# ElectronicATU.net
KiCad netlist of a schematic drawn in EAGLE
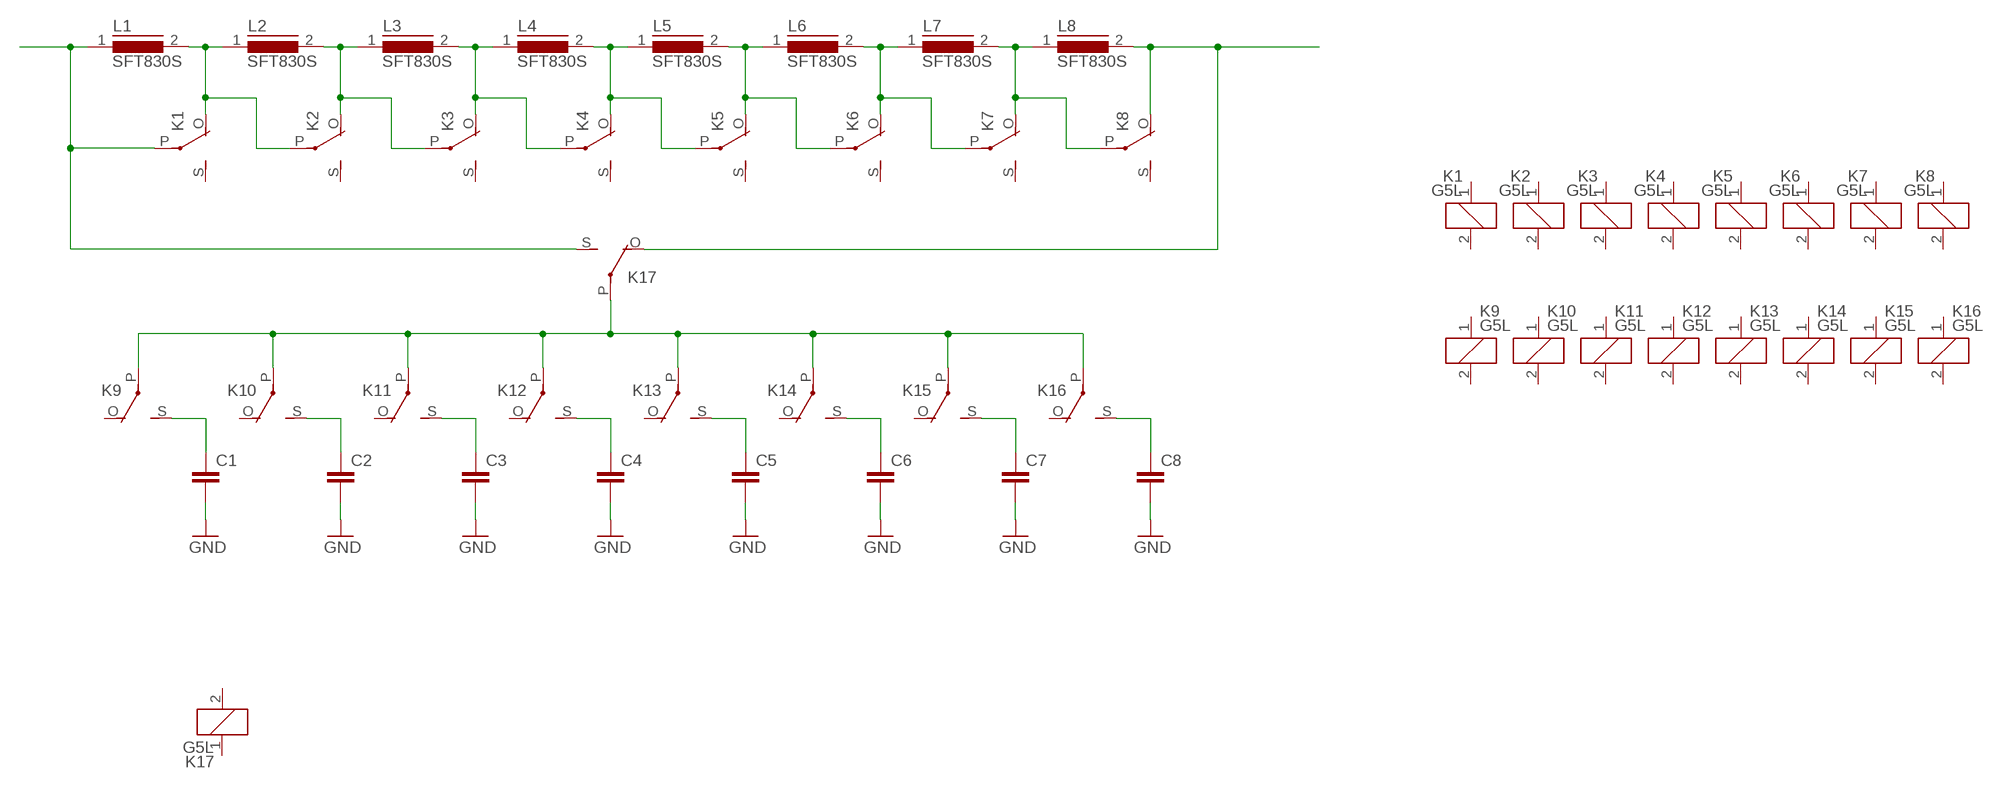
[diagram p0: schematic, sheet 1]

(export (version "E")
  (design (tool "Eeschema 10.0.6"))
  (components
    (comp (ref "C1")
      (value "C-EU075-042X103")
      (footprint "eagle-import:C075-042X103")
      (libsource (lib "eagle-import") (part "C-EU075-042X103"))
    )
    (comp (ref "C2")
      (value "C-EU075-042X103")
      (footprint "eagle-import:C075-042X103")
      (libsource (lib "eagle-import") (part "C-EU075-042X103"))
    )
    (comp (ref "C3")
      (value "C-EU075-042X103")
      (footprint "eagle-import:C075-042X103")
      (libsource (lib "eagle-import") (part "C-EU075-042X103"))
    )
    (comp (ref "C4")
      (value "C-EU075-042X103")
      (footprint "eagle-import:C075-042X103")
      (libsource (lib "eagle-import") (part "C-EU075-042X103"))
    )
    (comp (ref "C5")
      (value "C-EU075-042X103")
      (footprint "eagle-import:C075-042X103")
      (libsource (lib "eagle-import") (part "C-EU075-042X103"))
    )
    (comp (ref "C6")
      (value "C-EU075-042X103")
      (footprint "eagle-import:C075-042X103")
      (libsource (lib "eagle-import") (part "C-EU075-042X103"))
    )
    (comp (ref "C7")
      (value "C-EU075-042X103")
      (footprint "eagle-import:C075-042X103")
      (libsource (lib "eagle-import") (part "C-EU075-042X103"))
    )
    (comp (ref "C8")
      (value "C-EU075-042X103")
      (footprint "eagle-import:C075-042X103")
      (libsource (lib "eagle-import") (part "C-EU075-042X103"))
    )
    (comp (ref "K1")
      (value "G5L")
      (footprint "eagle-import:G5LE")
      (libsource (lib "eagle-import") (part "G5L"))
    )
    (comp (ref "K2")
      (value "G5L")
      (footprint "eagle-import:G5LE")
      (libsource (lib "eagle-import") (part "G5L"))
    )
    (comp (ref "K3")
      (value "G5L")
      (footprint "eagle-import:G5LE")
      (libsource (lib "eagle-import") (part "G5L"))
    )
    (comp (ref "K4")
      (value "G5L")
      (footprint "eagle-import:G5LE")
      (libsource (lib "eagle-import") (part "G5L"))
    )
    (comp (ref "K5")
      (value "G5L")
      (footprint "eagle-import:G5LE")
      (libsource (lib "eagle-import") (part "G5L"))
    )
    (comp (ref "K6")
      (value "G5L")
      (footprint "eagle-import:G5LE")
      (libsource (lib "eagle-import") (part "G5L"))
    )
    (comp (ref "K7")
      (value "G5L")
      (footprint "eagle-import:G5LE")
      (libsource (lib "eagle-import") (part "G5L"))
    )
    (comp (ref "K8")
      (value "G5L")
      (footprint "eagle-import:G5LE")
      (libsource (lib "eagle-import") (part "G5L"))
    )
    (comp (ref "K9")
      (value "G5L")
      (footprint "eagle-import:G5LE")
      (libsource (lib "eagle-import") (part "G5L"))
    )
    (comp (ref "K10")
      (value "G5L")
      (footprint "eagle-import:G5LE")
      (libsource (lib "eagle-import") (part "G5L"))
    )
    (comp (ref "K11")
      (value "G5L")
      (footprint "eagle-import:G5LE")
      (libsource (lib "eagle-import") (part "G5L"))
    )
    (comp (ref "K12")
      (value "G5L")
      (footprint "eagle-import:G5LE")
      (libsource (lib "eagle-import") (part "G5L"))
    )
    (comp (ref "K13")
      (value "G5L")
      (footprint "eagle-import:G5LE")
      (libsource (lib "eagle-import") (part "G5L"))
    )
    (comp (ref "K14")
      (value "G5L")
      (footprint "eagle-import:G5LE")
      (libsource (lib "eagle-import") (part "G5L"))
    )
    (comp (ref "K15")
      (value "G5L")
      (footprint "eagle-import:G5LE")
      (libsource (lib "eagle-import") (part "G5L"))
    )
    (comp (ref "K16")
      (value "G5L")
      (footprint "eagle-import:G5LE")
      (libsource (lib "eagle-import") (part "G5L"))
    )
    (comp (ref "K17")
      (value "G5L")
      (footprint "eagle-import:G5LE")
      (libsource (lib "eagle-import") (part "G5L"))
    )
    (comp (ref "L1")
      (value "SFT830S")
      (footprint "eagle-import:SFT830S")
      (libsource (lib "eagle-import") (part "SFT830S"))
    )
    (comp (ref "L2")
      (value "SFT830S")
      (footprint "eagle-import:SFT830S")
      (libsource (lib "eagle-import") (part "SFT830S"))
    )
    (comp (ref "L3")
      (value "SFT830S")
      (footprint "eagle-import:SFT830S")
      (libsource (lib "eagle-import") (part "SFT830S"))
    )
    (comp (ref "L4")
      (value "SFT830S")
      (footprint "eagle-import:SFT830S")
      (libsource (lib "eagle-import") (part "SFT830S"))
    )
    (comp (ref "L5")
      (value "SFT830S")
      (footprint "eagle-import:SFT830S")
      (libsource (lib "eagle-import") (part "SFT830S"))
    )
    (comp (ref "L6")
      (value "SFT830S")
      (footprint "eagle-import:SFT830S")
      (libsource (lib "eagle-import") (part "SFT830S"))
    )
    (comp (ref "L7")
      (value "SFT830S")
      (footprint "eagle-import:SFT830S")
      (libsource (lib "eagle-import") (part "SFT830S"))
    )
    (comp (ref "L8")
      (value "SFT830S")
      (footprint "eagle-import:SFT830S")
      (libsource (lib "eagle-import") (part "SFT830S"))
    )
  )
  (nets
    (net (code "1") (name "GND") (class "Default")
      (node (ref "C1") (pin "2") (pinfunction "2_2") (pintype "passive"))
      (node (ref "C2") (pin "2") (pinfunction "2_2") (pintype "passive"))
      (node (ref "C3") (pin "2") (pinfunction "2_2") (pintype "passive"))
      (node (ref "C4") (pin "2") (pinfunction "2_2") (pintype "passive"))
      (node (ref "C5") (pin "2") (pinfunction "2_2") (pintype "passive"))
      (node (ref "C6") (pin "2") (pinfunction "2_2") (pintype "passive"))
      (node (ref "C7") (pin "2") (pinfunction "2_2") (pintype "passive"))
      (node (ref "C8") (pin "2") (pinfunction "2_2") (pintype "passive"))
    )
    (net (code "2") (name "Net-(C1-Pad1)") (class "Default")
      (node (ref "C1") (pin "1") (pinfunction "1_1") (pintype "passive"))
      (node (ref "K9") (pin "S") (pinfunction "S_S") (pintype "passive"))
    )
    (net (code "3") (name "Net-(C2-Pad1)") (class "Default")
      (node (ref "C2") (pin "1") (pinfunction "1_1") (pintype "passive"))
      (node (ref "K10") (pin "S") (pinfunction "S_S") (pintype "passive"))
    )
    (net (code "4") (name "Net-(C3-Pad1)") (class "Default")
      (node (ref "C3") (pin "1") (pinfunction "1_1") (pintype "passive"))
      (node (ref "K11") (pin "S") (pinfunction "S_S") (pintype "passive"))
    )
    (net (code "5") (name "Net-(C4-Pad1)") (class "Default")
      (node (ref "C4") (pin "1") (pinfunction "1_1") (pintype "passive"))
      (node (ref "K12") (pin "S") (pinfunction "S_S") (pintype "passive"))
    )
    (net (code "6") (name "Net-(C5-Pad1)") (class "Default")
      (node (ref "C5") (pin "1") (pinfunction "1_1") (pintype "passive"))
      (node (ref "K13") (pin "S") (pinfunction "S_S") (pintype "passive"))
    )
    (net (code "7") (name "Net-(C6-Pad1)") (class "Default")
      (node (ref "C6") (pin "1") (pinfunction "1_1") (pintype "passive"))
      (node (ref "K14") (pin "S") (pinfunction "S_S") (pintype "passive"))
    )
    (net (code "8") (name "Net-(C7-Pad1)") (class "Default")
      (node (ref "C7") (pin "1") (pinfunction "1_1") (pintype "passive"))
      (node (ref "K15") (pin "S") (pinfunction "S_S") (pintype "passive"))
    )
    (net (code "9") (name "Net-(C8-Pad1)") (class "Default")
      (node (ref "C8") (pin "1") (pinfunction "1_1") (pintype "passive"))
      (node (ref "K16") (pin "S") (pinfunction "S_S") (pintype "passive"))
    )
    (net (code "10") (name "Net-(K1-PadO)") (class "Default")
      (node (ref "K1") (pin "O") (pinfunction "O_O") (pintype "passive"))
      (node (ref "K2") (pin "P") (pinfunction "P_P") (pintype "passive"))
      (node (ref "L1") (pin "2") (pinfunction "2_2") (pintype "passive"))
      (node (ref "L2") (pin "1") (pinfunction "1_1") (pintype "passive"))
    )
    (net (code "11") (name "Net-(K1-PadP)") (class "Default")
      (node (ref "K1") (pin "P") (pinfunction "P_P") (pintype "passive"))
      (node (ref "K17") (pin "S") (pinfunction "S_S") (pintype "passive"))
      (node (ref "L1") (pin "1") (pinfunction "1_1") (pintype "passive"))
    )
    (net (code "12") (name "Net-(K2-PadO)") (class "Default")
      (node (ref "K2") (pin "O") (pinfunction "O_O") (pintype "passive"))
      (node (ref "K3") (pin "P") (pinfunction "P_P") (pintype "passive"))
      (node (ref "L2") (pin "2") (pinfunction "2_2") (pintype "passive"))
      (node (ref "L3") (pin "1") (pinfunction "1_1") (pintype "passive"))
    )
    (net (code "13") (name "Net-(K3-PadO)") (class "Default")
      (node (ref "K3") (pin "O") (pinfunction "O_O") (pintype "passive"))
      (node (ref "K4") (pin "P") (pinfunction "P_P") (pintype "passive"))
      (node (ref "L3") (pin "2") (pinfunction "2_2") (pintype "passive"))
      (node (ref "L4") (pin "1") (pinfunction "1_1") (pintype "passive"))
    )
    (net (code "14") (name "Net-(K4-PadO)") (class "Default")
      (node (ref "K4") (pin "O") (pinfunction "O_O") (pintype "passive"))
      (node (ref "K5") (pin "P") (pinfunction "P_P") (pintype "passive"))
      (node (ref "L4") (pin "2") (pinfunction "2_2") (pintype "passive"))
      (node (ref "L5") (pin "1") (pinfunction "1_1") (pintype "passive"))
    )
    (net (code "15") (name "Net-(K5-PadO)") (class "Default")
      (node (ref "K5") (pin "O") (pinfunction "O_O") (pintype "passive"))
      (node (ref "K6") (pin "P") (pinfunction "P_P") (pintype "passive"))
      (node (ref "L5") (pin "2") (pinfunction "2_2") (pintype "passive"))
      (node (ref "L6") (pin "1") (pinfunction "1_1") (pintype "passive"))
    )
    (net (code "16") (name "Net-(K6-PadO)") (class "Default")
      (node (ref "K6") (pin "O") (pinfunction "O_O") (pintype "passive"))
      (node (ref "K7") (pin "P") (pinfunction "P_P") (pintype "passive"))
      (node (ref "L6") (pin "2") (pinfunction "2_2") (pintype "passive"))
      (node (ref "L7") (pin "1") (pinfunction "1_1") (pintype "passive"))
    )
    (net (code "17") (name "Net-(K7-PadO)") (class "Default")
      (node (ref "K7") (pin "O") (pinfunction "O_O") (pintype "passive"))
      (node (ref "K8") (pin "P") (pinfunction "P_P") (pintype "passive"))
      (node (ref "L7") (pin "2") (pinfunction "2_2") (pintype "passive"))
      (node (ref "L8") (pin "1") (pinfunction "1_1") (pintype "passive"))
    )
    (net (code "18") (name "Net-(K10-PadP)") (class "Default")
      (node (ref "K10") (pin "P") (pinfunction "P_P") (pintype "passive"))
      (node (ref "K11") (pin "P") (pinfunction "P_P") (pintype "passive"))
      (node (ref "K12") (pin "P") (pinfunction "P_P") (pintype "passive"))
      (node (ref "K13") (pin "P") (pinfunction "P_P") (pintype "passive"))
      (node (ref "K14") (pin "P") (pinfunction "P_P") (pintype "passive"))
      (node (ref "K15") (pin "P") (pinfunction "P_P") (pintype "passive"))
      (node (ref "K16") (pin "P") (pinfunction "P_P") (pintype "passive"))
      (node (ref "K17") (pin "P") (pinfunction "P_P") (pintype "passive"))
      (node (ref "K9") (pin "P") (pinfunction "P_P") (pintype "passive"))
    )
    (net (code "19") (name "Net-(K17-PadO)") (class "Default")
      (node (ref "K17") (pin "O") (pinfunction "O_O") (pintype "passive"))
      (node (ref "K8") (pin "O") (pinfunction "O_O") (pintype "passive"))
      (node (ref "L8") (pin "2") (pinfunction "2_2") (pintype "passive"))
    )
    (net (code "20") (name "unconnected-(K1-Pad1)") (class "Default")
      (node (ref "K1") (pin "1") (pinfunction "1_1") (pintype "passive"))
    )
    (net (code "21") (name "unconnected-(K1-Pad2)") (class "Default")
      (node (ref "K1") (pin "2") (pinfunction "2_2") (pintype "passive"))
    )
    (net (code "22") (name "unconnected-(K1-PadS)") (class "Default")
      (node (ref "K1") (pin "S") (pinfunction "S_S") (pintype "passive"))
    )
    (net (code "23") (name "unconnected-(K2-Pad1)") (class "Default")
      (node (ref "K2") (pin "1") (pinfunction "1_1") (pintype "passive"))
    )
    (net (code "24") (name "unconnected-(K2-Pad2)") (class "Default")
      (node (ref "K2") (pin "2") (pinfunction "2_2") (pintype "passive"))
    )
    (net (code "25") (name "unconnected-(K2-PadS)") (class "Default")
      (node (ref "K2") (pin "S") (pinfunction "S_S") (pintype "passive"))
    )
    (net (code "26") (name "unconnected-(K3-Pad1)") (class "Default")
      (node (ref "K3") (pin "1") (pinfunction "1_1") (pintype "passive"))
    )
    (net (code "27") (name "unconnected-(K3-Pad2)") (class "Default")
      (node (ref "K3") (pin "2") (pinfunction "2_2") (pintype "passive"))
    )
    (net (code "28") (name "unconnected-(K3-PadS)") (class "Default")
      (node (ref "K3") (pin "S") (pinfunction "S_S") (pintype "passive"))
    )
    (net (code "29") (name "unconnected-(K4-Pad1)") (class "Default")
      (node (ref "K4") (pin "1") (pinfunction "1_1") (pintype "passive"))
    )
    (net (code "30") (name "unconnected-(K4-Pad2)") (class "Default")
      (node (ref "K4") (pin "2") (pinfunction "2_2") (pintype "passive"))
    )
    (net (code "31") (name "unconnected-(K4-PadS)") (class "Default")
      (node (ref "K4") (pin "S") (pinfunction "S_S") (pintype "passive"))
    )
    (net (code "32") (name "unconnected-(K5-Pad1)") (class "Default")
      (node (ref "K5") (pin "1") (pinfunction "1_1") (pintype "passive"))
    )
    (net (code "33") (name "unconnected-(K5-Pad2)") (class "Default")
      (node (ref "K5") (pin "2") (pinfunction "2_2") (pintype "passive"))
    )
    (net (code "34") (name "unconnected-(K5-PadS)") (class "Default")
      (node (ref "K5") (pin "S") (pinfunction "S_S") (pintype "passive"))
    )
    (net (code "35") (name "unconnected-(K6-Pad1)") (class "Default")
      (node (ref "K6") (pin "1") (pinfunction "1_1") (pintype "passive"))
    )
    (net (code "36") (name "unconnected-(K6-Pad2)") (class "Default")
      (node (ref "K6") (pin "2") (pinfunction "2_2") (pintype "passive"))
    )
    (net (code "37") (name "unconnected-(K6-PadS)") (class "Default")
      (node (ref "K6") (pin "S") (pinfunction "S_S") (pintype "passive"))
    )
    (net (code "38") (name "unconnected-(K7-Pad1)") (class "Default")
      (node (ref "K7") (pin "1") (pinfunction "1_1") (pintype "passive"))
    )
    (net (code "39") (name "unconnected-(K7-Pad2)") (class "Default")
      (node (ref "K7") (pin "2") (pinfunction "2_2") (pintype "passive"))
    )
    (net (code "40") (name "unconnected-(K7-PadS)") (class "Default")
      (node (ref "K7") (pin "S") (pinfunction "S_S") (pintype "passive"))
    )
    (net (code "41") (name "unconnected-(K8-Pad1)") (class "Default")
      (node (ref "K8") (pin "1") (pinfunction "1_1") (pintype "passive"))
    )
    (net (code "42") (name "unconnected-(K8-Pad2)") (class "Default")
      (node (ref "K8") (pin "2") (pinfunction "2_2") (pintype "passive"))
    )
    (net (code "43") (name "unconnected-(K8-PadS)") (class "Default")
      (node (ref "K8") (pin "S") (pinfunction "S_S") (pintype "passive"))
    )
    (net (code "44") (name "unconnected-(K9-Pad1)") (class "Default")
      (node (ref "K9") (pin "1") (pinfunction "1_1") (pintype "passive"))
    )
    (net (code "45") (name "unconnected-(K9-Pad2)") (class "Default")
      (node (ref "K9") (pin "2") (pinfunction "2_2") (pintype "passive"))
    )
    (net (code "46") (name "unconnected-(K9-PadO)") (class "Default")
      (node (ref "K9") (pin "O") (pinfunction "O_O") (pintype "passive"))
    )
    (net (code "47") (name "unconnected-(K10-Pad1)") (class "Default")
      (node (ref "K10") (pin "1") (pinfunction "1_1") (pintype "passive"))
    )
    (net (code "48") (name "unconnected-(K10-Pad2)") (class "Default")
      (node (ref "K10") (pin "2") (pinfunction "2_2") (pintype "passive"))
    )
    (net (code "49") (name "unconnected-(K10-PadO)") (class "Default")
      (node (ref "K10") (pin "O") (pinfunction "O_O") (pintype "passive"))
    )
    (net (code "50") (name "unconnected-(K11-Pad1)") (class "Default")
      (node (ref "K11") (pin "1") (pinfunction "1_1") (pintype "passive"))
    )
    (net (code "51") (name "unconnected-(K11-Pad2)") (class "Default")
      (node (ref "K11") (pin "2") (pinfunction "2_2") (pintype "passive"))
    )
    (net (code "52") (name "unconnected-(K11-PadO)") (class "Default")
      (node (ref "K11") (pin "O") (pinfunction "O_O") (pintype "passive"))
    )
    (net (code "53") (name "unconnected-(K12-Pad1)") (class "Default")
      (node (ref "K12") (pin "1") (pinfunction "1_1") (pintype "passive"))
    )
    (net (code "54") (name "unconnected-(K12-Pad2)") (class "Default")
      (node (ref "K12") (pin "2") (pinfunction "2_2") (pintype "passive"))
    )
    (net (code "55") (name "unconnected-(K12-PadO)") (class "Default")
      (node (ref "K12") (pin "O") (pinfunction "O_O") (pintype "passive"))
    )
    (net (code "56") (name "unconnected-(K13-Pad1)") (class "Default")
      (node (ref "K13") (pin "1") (pinfunction "1_1") (pintype "passive"))
    )
    (net (code "57") (name "unconnected-(K13-Pad2)") (class "Default")
      (node (ref "K13") (pin "2") (pinfunction "2_2") (pintype "passive"))
    )
    (net (code "58") (name "unconnected-(K13-PadO)") (class "Default")
      (node (ref "K13") (pin "O") (pinfunction "O_O") (pintype "passive"))
    )
    (net (code "59") (name "unconnected-(K14-Pad1)") (class "Default")
      (node (ref "K14") (pin "1") (pinfunction "1_1") (pintype "passive"))
    )
    (net (code "60") (name "unconnected-(K14-Pad2)") (class "Default")
      (node (ref "K14") (pin "2") (pinfunction "2_2") (pintype "passive"))
    )
    (net (code "61") (name "unconnected-(K14-PadO)") (class "Default")
      (node (ref "K14") (pin "O") (pinfunction "O_O") (pintype "passive"))
    )
    (net (code "62") (name "unconnected-(K15-Pad1)") (class "Default")
      (node (ref "K15") (pin "1") (pinfunction "1_1") (pintype "passive"))
    )
    (net (code "63") (name "unconnected-(K15-Pad2)") (class "Default")
      (node (ref "K15") (pin "2") (pinfunction "2_2") (pintype "passive"))
    )
    (net (code "64") (name "unconnected-(K15-PadO)") (class "Default")
      (node (ref "K15") (pin "O") (pinfunction "O_O") (pintype "passive"))
    )
    (net (code "65") (name "unconnected-(K16-Pad1)") (class "Default")
      (node (ref "K16") (pin "1") (pinfunction "1_1") (pintype "passive"))
    )
    (net (code "66") (name "unconnected-(K16-Pad2)") (class "Default")
      (node (ref "K16") (pin "2") (pinfunction "2_2") (pintype "passive"))
    )
    (net (code "67") (name "unconnected-(K16-PadO)") (class "Default")
      (node (ref "K16") (pin "O") (pinfunction "O_O") (pintype "passive"))
    )
    (net (code "68") (name "unconnected-(K17-Pad1)") (class "Default")
      (node (ref "K17") (pin "1") (pinfunction "1_1") (pintype "passive"))
    )
    (net (code "69") (name "unconnected-(K17-Pad2)") (class "Default")
      (node (ref "K17") (pin "2") (pinfunction "2_2") (pintype "passive"))
    )
  )
)
